# PowerSupply.net
KiCad netlist of a schematic drawn in Altium Designer
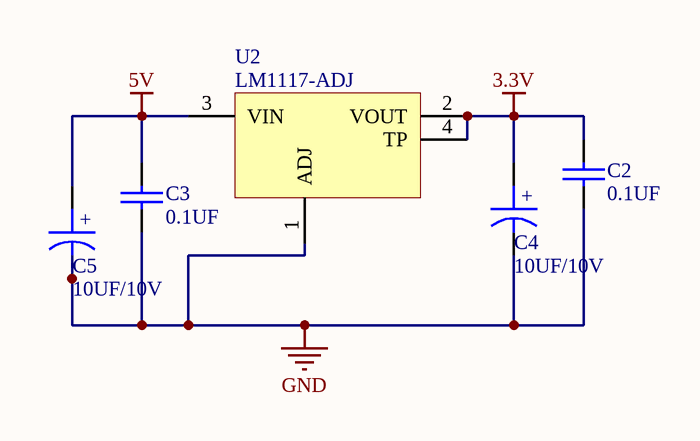
[diagram p0: PowerSupply.SchDoc]

(export (version "E")
  (design (tool "Eeschema 10.0.6"))
  (components
    (comp (ref "C2") (value "0.1UF") (footprint "CAPC0603") (libsource (lib "Devices") (part "CAP NP")))
    (comp (ref "C3") (value "0.1UF") (footprint "CAPC0603") (libsource (lib "Devices") (part "CAP NP")))
    (comp (ref "C4")
      (value "10UF/10V")
      (footprint "CAPC1206_TANTALUM")
      (libsource (lib "Devices") (part "CAP"))
    )
    (comp (ref "C5")
      (value "10UF/10V")
      (footprint "CAPC1206_TANTALUM")
      (libsource (lib "Devices") (part "CAP"))
    )
    (comp (ref "U2")
      (value "LM1117-ADJ")
      (footprint "SOT223")
      (description "3.3V LDO REGULATOR")
      (libsource (lib "CustomParts") (part "LM1117-3.3V_ADJ"))
    )
  )
  (nets
    (net (code "1") (name "3.3V") (class "Default")
      (node (ref "C2") (pin "1") (pintype "passive"))
      (node (ref "C4") (pin "1") (pinfunction "1_1") (pintype "passive"))
      (node (ref "U2") (pin "2") (pinfunction "VOUT_2") (pintype "power_in"))
      (node (ref "U2") (pin "4") (pinfunction "TP_4") (pintype "power_in"))
    )
    (net (code "2") (name "5V") (class "Default")
      (node (ref "C3") (pin "1") (pintype "passive"))
      (node (ref "C5") (pin "1") (pinfunction "1_1") (pintype "passive"))
      (node (ref "U2") (pin "3") (pinfunction "VIN_3") (pintype "power_in"))
    )
    (net (code "3") (name "GND") (class "Default")
      (node (ref "C2") (pin "2") (pintype "passive"))
      (node (ref "C3") (pin "2") (pintype "passive"))
      (node (ref "C4") (pin "2") (pinfunction "2_2") (pintype "passive"))
      (node (ref "C5") (pin "2") (pinfunction "2_2") (pintype "passive"))
      (node (ref "U2") (pin "1") (pinfunction "ADJ_1") (pintype "power_in"))
    )
  )
)
